# motorController.net
KiCad netlist of a schematic drawn in Altium Designer
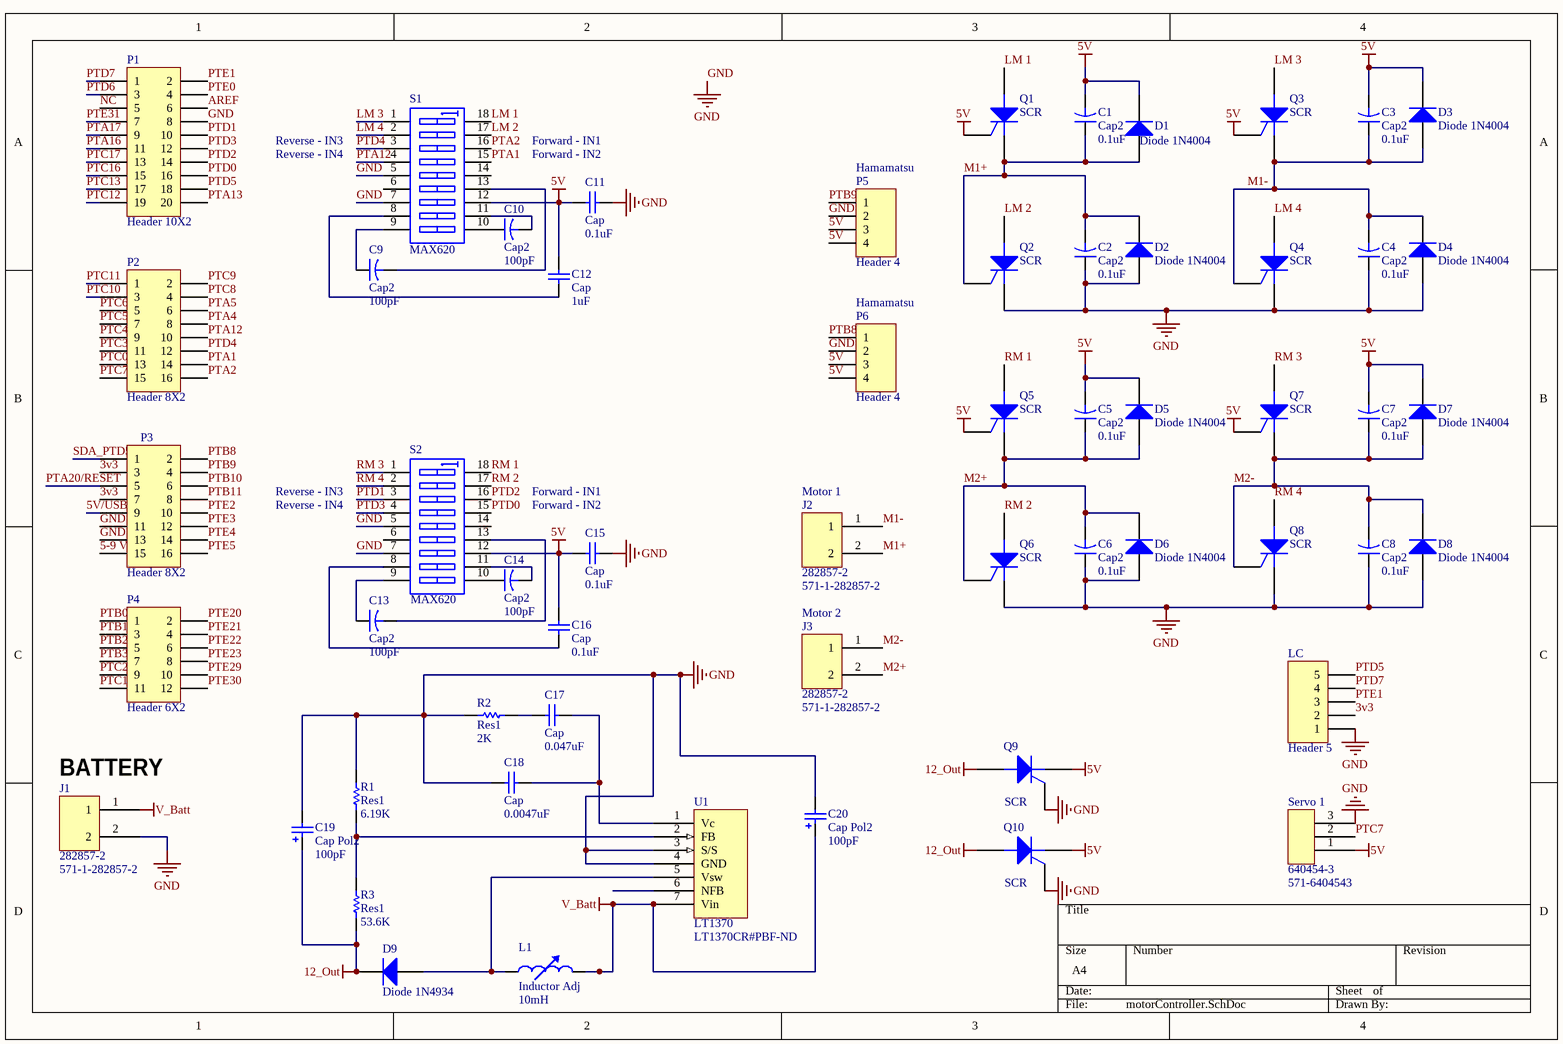
[diagram p0: motorController.SchDoc]

(export (version "E")
  (design (tool "Eeschema 10.0.6"))
  (components
    (comp (ref "C1")
      (value "Cap2")
      (footprint "CAPR5-4X5")
      (description "Capacitor")
      (fields (field (name "ALTIUM_VALUE") "0.1uF") (field (name "PUBLISHER") "Altium Limited"))
      (libsource (lib "Miscellaneous Devices") (part "Cap2"))
    )
    (comp (ref "C2")
      (value "Cap2")
      (footprint "CAPR5-4X5")
      (description "Capacitor")
      (fields (field (name "ALTIUM_VALUE") "0.1uF") (field (name "PUBLISHER") "Altium Limited"))
      (libsource (lib "Miscellaneous Devices") (part "Cap2"))
    )
    (comp (ref "C3")
      (value "Cap2")
      (footprint "CAPR5-4X5")
      (description "Capacitor")
      (fields (field (name "ALTIUM_VALUE") "0.1uF") (field (name "PUBLISHER") "Altium Limited"))
      (libsource (lib "Miscellaneous Devices") (part "Cap2"))
    )
    (comp (ref "C4")
      (value "Cap2")
      (footprint "CAPR5-4X5")
      (description "Capacitor")
      (fields (field (name "ALTIUM_VALUE") "0.1uF") (field (name "PUBLISHER") "Altium Limited"))
      (libsource (lib "Miscellaneous Devices") (part "Cap2"))
    )
    (comp (ref "C5")
      (value "Cap2")
      (footprint "CAPR5-4X5")
      (description "Capacitor")
      (fields (field (name "ALTIUM_VALUE") "0.1uF") (field (name "PUBLISHER") "Altium Limited"))
      (libsource (lib "Miscellaneous Devices") (part "Cap2"))
    )
    (comp (ref "C6")
      (value "Cap2")
      (footprint "CAPR5-4X5")
      (description "Capacitor")
      (fields (field (name "ALTIUM_VALUE") "0.1uF") (field (name "PUBLISHER") "Altium Limited"))
      (libsource (lib "Miscellaneous Devices") (part "Cap2"))
    )
    (comp (ref "C7")
      (value "Cap2")
      (footprint "CAPR5-4X5")
      (description "Capacitor")
      (fields (field (name "ALTIUM_VALUE") "0.1uF") (field (name "PUBLISHER") "Altium Limited"))
      (libsource (lib "Miscellaneous Devices") (part "Cap2"))
    )
    (comp (ref "C8")
      (value "Cap2")
      (footprint "CAPR5-4X5")
      (description "Capacitor")
      (fields (field (name "ALTIUM_VALUE") "0.1uF") (field (name "PUBLISHER") "Altium Limited"))
      (libsource (lib "Miscellaneous Devices") (part "Cap2"))
    )
    (comp (ref "C9")
      (value "Cap2")
      (footprint "CAPR5-4X5")
      (description "Capacitor")
      (fields (field (name "ALTIUM_VALUE") "100pF") (field (name "PUBLISHER") "Altium Limited"))
      (libsource (lib "Miscellaneous Devices") (part "Cap2"))
    )
    (comp (ref "C10")
      (value "Cap2")
      (footprint "CAPR5-4X5")
      (description "Capacitor")
      (fields (field (name "ALTIUM_VALUE") "100pF") (field (name "PUBLISHER") "Altium Limited"))
      (libsource (lib "Miscellaneous Devices") (part "Cap2"))
    )
    (comp (ref "C11")
      (value "Cap")
      (footprint "RAD-0.3")
      (description "Capacitor")
      (fields (field (name "ALTIUM_VALUE") "0.1uF") (field (name "PUBLISHER") "Altium Limited"))
      (libsource (lib "Miscellaneous Devices") (part "Cap"))
    )
    (comp (ref "C12")
      (value "Cap")
      (footprint "RAD-0.3")
      (description "Capacitor")
      (fields (field (name "ALTIUM_VALUE") "1uF") (field (name "PUBLISHER") "Altium Limited"))
      (libsource (lib "Miscellaneous Devices") (part "Cap"))
    )
    (comp (ref "C13")
      (value "Cap2")
      (footprint "CAPR5-4X5")
      (description "Capacitor")
      (fields (field (name "ALTIUM_VALUE") "100pF") (field (name "PUBLISHER") "Altium Limited"))
      (libsource (lib "Miscellaneous Devices") (part "Cap2"))
    )
    (comp (ref "C14")
      (value "Cap2")
      (footprint "CAPR5-4X5")
      (description "Capacitor")
      (fields (field (name "ALTIUM_VALUE") "100pF") (field (name "PUBLISHER") "Altium Limited"))
      (libsource (lib "Miscellaneous Devices") (part "Cap2"))
    )
    (comp (ref "C15")
      (value "Cap")
      (footprint "RAD-0.3")
      (description "Capacitor")
      (fields (field (name "ALTIUM_VALUE") "0.1uF") (field (name "PUBLISHER") "Altium Limited"))
      (libsource (lib "Miscellaneous Devices") (part "Cap"))
    )
    (comp (ref "C16")
      (value "Cap")
      (footprint "RAD-0.3")
      (description "Capacitor")
      (fields (field (name "ALTIUM_VALUE") "0.1uF") (field (name "PUBLISHER") "Altium Limited"))
      (libsource (lib "Miscellaneous Devices") (part "Cap"))
    )
    (comp (ref "C17")
      (value "Cap")
      (footprint "RAD-0.3")
      (description "Capacitor")
      (fields (field (name "ALTIUM_VALUE") "0.047uF") (field (name "PUBLISHER") "Altium Limited"))
      (libsource (lib "Miscellaneous Devices") (part "Cap"))
    )
    (comp (ref "C18")
      (value "Cap")
      (footprint "RAD-0.3")
      (description "Capacitor")
      (fields (field (name "ALTIUM_VALUE") "0.0047uF") (field (name "PUBLISHER") "Altium Limited"))
      (libsource (lib "Miscellaneous Devices") (part "Cap"))
    )
    (comp (ref "C19")
      (value "Cap Pol2")
      (footprint "POLAR0.8")
      (description "Polarized Capacitor (Axial)")
      (fields (field (name "ALTIUM_VALUE") "100pF") (field (name "PUBLISHER") "Altium Limited"))
      (libsource (lib "Miscellaneous Devices") (part "Cap Pol2"))
    )
    (comp (ref "C20")
      (value "Cap Pol2")
      (footprint "POLAR0.8")
      (description "Polarized Capacitor (Axial)")
      (fields (field (name "ALTIUM_VALUE") "100pF") (field (name "PUBLISHER") "Altium Limited"))
      (libsource (lib "Miscellaneous Devices") (part "Cap Pol2"))
    )
    (comp (ref "D1")
      (value "Diode 1N4004")
      (footprint "DO-41")
      (description "1 Amp General Purpose Rectifier")
      (fields (field (name "PUBLISHER") "Altium Limited"))
      (libsource (lib "Miscellaneous Devices") (part "Diode 1N4004"))
    )
    (comp (ref "D2")
      (value "Diode 1N4004")
      (footprint "DO-41")
      (description "1 Amp General Purpose Rectifier")
      (fields (field (name "PUBLISHER") "Altium Limited"))
      (libsource (lib "Miscellaneous Devices") (part "Diode 1N4004"))
    )
    (comp (ref "D3")
      (value "Diode 1N4004")
      (footprint "DO-41")
      (description "1 Amp General Purpose Rectifier")
      (fields (field (name "PUBLISHER") "Altium Limited"))
      (libsource (lib "Miscellaneous Devices") (part "Diode 1N4004"))
    )
    (comp (ref "D4")
      (value "Diode 1N4004")
      (footprint "DO-41")
      (description "1 Amp General Purpose Rectifier")
      (fields (field (name "PUBLISHER") "Altium Limited"))
      (libsource (lib "Miscellaneous Devices") (part "Diode 1N4004"))
    )
    (comp (ref "D5")
      (value "Diode 1N4004")
      (footprint "DO-41")
      (description "1 Amp General Purpose Rectifier")
      (fields (field (name "PUBLISHER") "Altium Limited"))
      (libsource (lib "Miscellaneous Devices") (part "Diode 1N4004"))
    )
    (comp (ref "D6")
      (value "Diode 1N4004")
      (footprint "DO-41")
      (description "1 Amp General Purpose Rectifier")
      (fields (field (name "PUBLISHER") "Altium Limited"))
      (libsource (lib "Miscellaneous Devices") (part "Diode 1N4004"))
    )
    (comp (ref "D7")
      (value "Diode 1N4004")
      (footprint "DO-41")
      (description "1 Amp General Purpose Rectifier")
      (fields (field (name "PUBLISHER") "Altium Limited"))
      (libsource (lib "Miscellaneous Devices") (part "Diode 1N4004"))
    )
    (comp (ref "D8")
      (value "Diode 1N4004")
      (footprint "DO-41")
      (description "1 Amp General Purpose Rectifier")
      (fields (field (name "PUBLISHER") "Altium Limited"))
      (libsource (lib "Miscellaneous Devices") (part "Diode 1N4004"))
    )
    (comp (ref "D9")
      (value "Diode 1N4934")
      (footprint "DO-41")
      (description "1 Amp Fast Recovery Rectifier")
      (fields (field (name "PUBLISHER") "Altium Limited"))
      (libsource (lib "Miscellaneous Devices") (part "Diode 1N4934"))
    )
    (comp (ref "J1")
      (value "282857-2")
      (footprint "282857-2")
      (fields (field (name "SUPPLIER PART NUMBER 1") "571-1-282857-2"))
      (libsource (lib "TE_Connectors") (part "282857-2"))
    )
    (comp (ref "J2")
      (value "282857-2")
      (footprint "282857-2")
      (fields (field (name "SUPPLIER PART NUMBER 1") "571-1-282857-2"))
      (libsource (lib "TE_Connectors") (part "282857-2"))
    )
    (comp (ref "J3")
      (value "282857-2")
      (footprint "282857-2")
      (fields (field (name "SUPPLIER PART NUMBER 1") "571-1-282857-2"))
      (libsource (lib "TE_Connectors") (part "282857-2"))
    )
    (comp (ref "L1")
      (value "Inductor Adj")
      (footprint "AXIAL-0.8")
      (description "Adjustable Inductor")
      (fields (field (name "ALTIUM_VALUE") "10mH") (field (name "PUBLISHER") "Altium Limited"))
      (libsource (lib "Miscellaneous Devices") (part "Inductor Adj"))
    )
    (comp (ref "LC")
      (value "Header 5")
      (footprint "HDR1X5")
      (description "Header, 5-Pin")
      (fields (field (name "PUBLISHER") "Altium Limited"))
      (libsource (lib "Miscellaneous Connectors") (part "Header 5"))
    )
    (comp (ref "P1")
      (value "Header 10X2")
      (footprint "HDR2X10")
      (description "Header, 10-Pin, Dual row")
      (fields (field (name "PUBLISHER") "Altium Limited"))
      (libsource (lib "Miscellaneous Connectors") (part "Header 10X2"))
    )
    (comp (ref "P2")
      (value "Header 8X2")
      (footprint "HDR2X8")
      (description "Header, 8-Pin, Dual row")
      (fields (field (name "PUBLISHER") "Altium Limited"))
      (libsource (lib "Miscellaneous Connectors") (part "Header 8X2"))
    )
    (comp (ref "P3")
      (value "Header 8X2")
      (footprint "HDR2X8")
      (description "Header, 8-Pin, Dual row")
      (fields (field (name "PUBLISHER") "Altium Limited"))
      (libsource (lib "Miscellaneous Connectors") (part "Header 8X2"))
    )
    (comp (ref "P4")
      (value "Header 6X2")
      (footprint "HDR2X6")
      (description "Header, 6-Pin, Dual row")
      (fields (field (name "PUBLISHER") "Altium Limited"))
      (libsource (lib "Miscellaneous Connectors") (part "Header 6X2"))
    )
    (comp (ref "P5")
      (value "Header 4")
      (footprint "HDR1X4")
      (description "Header, 4-Pin")
      (fields (field (name "PUBLISHER") "Altium Limited"))
      (libsource (lib "Miscellaneous Connectors") (part "Header 4"))
    )
    (comp (ref "P6")
      (value "Header 4")
      (footprint "HDR1X4")
      (description "Header, 4-Pin")
      (fields (field (name "PUBLISHER") "Altium Limited"))
      (libsource (lib "Miscellaneous Connectors") (part "Header 4"))
    )
    (comp (ref "Q1")
      (value "SCR")
      (footprint "TO-220-AB")
      (description "Silicon Controlled Rectifier")
      (fields (field (name "PUBLISHER") "Altium Limited"))
      (libsource (lib "Miscellaneous Devices") (part "SCR"))
    )
    (comp (ref "Q2")
      (value "SCR")
      (footprint "TO-220-AB")
      (description "Silicon Controlled Rectifier")
      (fields (field (name "PUBLISHER") "Altium Limited"))
      (libsource (lib "Miscellaneous Devices") (part "SCR"))
    )
    (comp (ref "Q3")
      (value "SCR")
      (footprint "TO-220-AB")
      (description "Silicon Controlled Rectifier")
      (fields (field (name "PUBLISHER") "Altium Limited"))
      (libsource (lib "Miscellaneous Devices") (part "SCR"))
    )
    (comp (ref "Q4")
      (value "SCR")
      (footprint "TO-220-AB")
      (description "Silicon Controlled Rectifier")
      (fields (field (name "PUBLISHER") "Altium Limited"))
      (libsource (lib "Miscellaneous Devices") (part "SCR"))
    )
    (comp (ref "Q5")
      (value "SCR")
      (footprint "TO-220-AB")
      (description "Silicon Controlled Rectifier")
      (fields (field (name "PUBLISHER") "Altium Limited"))
      (libsource (lib "Miscellaneous Devices") (part "SCR"))
    )
    (comp (ref "Q6")
      (value "SCR")
      (footprint "TO-220-AB")
      (description "Silicon Controlled Rectifier")
      (fields (field (name "PUBLISHER") "Altium Limited"))
      (libsource (lib "Miscellaneous Devices") (part "SCR"))
    )
    (comp (ref "Q7")
      (value "SCR")
      (footprint "TO-220-AB")
      (description "Silicon Controlled Rectifier")
      (fields (field (name "PUBLISHER") "Altium Limited"))
      (libsource (lib "Miscellaneous Devices") (part "SCR"))
    )
    (comp (ref "Q8")
      (value "SCR")
      (footprint "TO-220-AB")
      (description "Silicon Controlled Rectifier")
      (fields (field (name "PUBLISHER") "Altium Limited"))
      (libsource (lib "Miscellaneous Devices") (part "SCR"))
    )
    (comp (ref "Q9")
      (value "SCR")
      (footprint "TO-220-AB")
      (description "Silicon Controlled Rectifier")
      (fields (field (name "PUBLISHER") "Altium Limited"))
      (libsource (lib "Miscellaneous Devices") (part "SCR"))
    )
    (comp (ref "Q10")
      (value "SCR")
      (footprint "TO-220-AB")
      (description "Silicon Controlled Rectifier")
      (fields (field (name "PUBLISHER") "Altium Limited"))
      (libsource (lib "Miscellaneous Devices") (part "SCR"))
    )
    (comp (ref "R1")
      (value "Res1")
      (footprint "AXIAL-0.3")
      (description "Resistor")
      (fields (field (name "ALTIUM_VALUE") "6.19K") (field (name "PUBLISHER") "Altium Limited"))
      (libsource (lib "Miscellaneous Devices") (part "Res1"))
    )
    (comp (ref "R2")
      (value "Res1")
      (footprint "AXIAL-0.3")
      (description "Resistor")
      (fields (field (name "ALTIUM_VALUE") "2K") (field (name "PUBLISHER") "Altium Limited"))
      (libsource (lib "Miscellaneous Devices") (part "Res1"))
    )
    (comp (ref "R3")
      (value "Res1")
      (footprint "AXIAL-0.3")
      (description "Resistor")
      (fields (field (name "ALTIUM_VALUE") "53.6K") (field (name "PUBLISHER") "Altium Limited"))
      (libsource (lib "Miscellaneous Devices") (part "Res1"))
    )
    (comp (ref "S1")
      (value "MAX620")
      (footprint "DIP-18")
      (description "DIP Switch, 9 Position, SPST")
      (fields (field (name "PUBLISHER") "Altium Limited"))
      (libsource (lib "Miscellaneous Devices") (part "SW DIP-9"))
    )
    (comp (ref "S2")
      (value "MAX620")
      (footprint "DIP-18")
      (description "DIP Switch, 9 Position, SPST")
      (fields (field (name "PUBLISHER") "Altium Limited"))
      (libsource (lib "Miscellaneous Devices") (part "SW DIP-9"))
    )
    (comp (ref "Servo 1")
      (value "640454-3")
      (footprint "6404543")
      (description "Headers & Wire Housings POLARIZED HEADER 3P Straight Post tin")
      (fields (field (name "SUPPLIER PART NUMBER 1") "571-6404543"))
      (libsource (lib "TE_Connectors") (part "640454-3"))
    )
    (comp (ref "U1")
      (value "LT1370")
      (footprint "DDPak7")
      (fields (field (name "SUPPLIER PART NUMBER 1") "LT1370CR#PBF-ND"))
      (libsource (lib "Switching_Regulators") (part "LT1370"))
    )
  )
  (nets
    (net (code "1") (name "/3v3") (class "Default")
      (node (ref "LC") (pin "2") (pinfunction "2_2") (pintype "passive"))
      (node (ref "P3") (pin "3") (pinfunction "3_3") (pintype "passive"))
      (node (ref "P3") (pin "7") (pinfunction "7_7") (pintype "passive"))
    )
    (net (code "2") (name "/5-9 Vin") (class "Default")
      (node (ref "P3") (pin "15") (pinfunction "15_15") (pintype "passive"))
    )
    (net (code "3") (name "/5V{slash}USB") (class "Default")
      (node (ref "P3") (pin "9") (pinfunction "9_9") (pintype "passive"))
    )
    (net (code "4") (name "/AREF") (class "Default")
      (node (ref "P1") (pin "6") (pinfunction "6_6") (pintype "passive"))
    )
    (net (code "5") (name "/LM 1") (class "Default")
      (node (ref "Q1") (pin "1") (pinfunction "A_1") (pintype "passive"))
      (node (ref "S1") (pin "18") (pinfunction "B1_18") (pintype "passive"))
    )
    (net (code "6") (name "/LM 2") (class "Default")
      (node (ref "Q2") (pin "1") (pinfunction "A_1") (pintype "passive"))
      (node (ref "S1") (pin "17") (pinfunction "B2_17") (pintype "passive"))
    )
    (net (code "7") (name "/LM 3") (class "Default")
      (node (ref "Q3") (pin "1") (pinfunction "A_1") (pintype "passive"))
      (node (ref "S1") (pin "1") (pinfunction "A1_1") (pintype "passive"))
    )
    (net (code "8") (name "/LM 4") (class "Default")
      (node (ref "Q4") (pin "1") (pinfunction "A_1") (pintype "passive"))
      (node (ref "S1") (pin "2") (pinfunction "A2_2") (pintype "passive"))
    )
    (net (code "9") (name "/M1+") (class "Default")
      (node (ref "C1") (pin "1") (pinfunction "1_1") (pintype "passive"))
      (node (ref "C2") (pin "2") (pinfunction "2_2") (pintype "passive"))
      (node (ref "D1") (pin "1") (pinfunction "A_1") (pintype "passive"))
      (node (ref "D2") (pin "2") (pinfunction "K_2") (pintype "passive"))
      (node (ref "J2") (pin "2") (pinfunction "2_2") (pintype "passive"))
      (node (ref "Q1") (pin "3") (pinfunction "K_3") (pintype "passive"))
      (node (ref "Q2") (pin "2") (pinfunction "G_2") (pintype "passive"))
    )
    (net (code "10") (name "/M1-") (class "Default")
      (node (ref "C3") (pin "1") (pinfunction "1_1") (pintype "passive"))
      (node (ref "C4") (pin "2") (pinfunction "2_2") (pintype "passive"))
      (node (ref "D3") (pin "1") (pinfunction "A_1") (pintype "passive"))
      (node (ref "D4") (pin "2") (pinfunction "K_2") (pintype "passive"))
      (node (ref "J2") (pin "1") (pinfunction "1_1") (pintype "passive"))
      (node (ref "Q3") (pin "3") (pinfunction "K_3") (pintype "passive"))
      (node (ref "Q4") (pin "2") (pinfunction "G_2") (pintype "passive"))
    )
    (net (code "11") (name "/M2+") (class "Default")
      (node (ref "C5") (pin "1") (pinfunction "1_1") (pintype "passive"))
      (node (ref "C6") (pin "2") (pinfunction "2_2") (pintype "passive"))
      (node (ref "D5") (pin "1") (pinfunction "A_1") (pintype "passive"))
      (node (ref "D6") (pin "2") (pinfunction "K_2") (pintype "passive"))
      (node (ref "J3") (pin "2") (pinfunction "2_2") (pintype "passive"))
      (node (ref "Q5") (pin "3") (pinfunction "K_3") (pintype "passive"))
      (node (ref "Q6") (pin "2") (pinfunction "G_2") (pintype "passive"))
    )
    (net (code "12") (name "/M2-") (class "Default")
      (node (ref "C7") (pin "1") (pinfunction "1_1") (pintype "passive"))
      (node (ref "C8") (pin "2") (pinfunction "2_2") (pintype "passive"))
      (node (ref "D7") (pin "1") (pinfunction "A_1") (pintype "passive"))
      (node (ref "D8") (pin "2") (pinfunction "K_2") (pintype "passive"))
      (node (ref "J3") (pin "1") (pinfunction "1_1") (pintype "passive"))
      (node (ref "Q7") (pin "3") (pinfunction "K_3") (pintype "passive"))
      (node (ref "Q8") (pin "2") (pinfunction "G_2") (pintype "passive"))
    )
    (net (code "13") (name "/NC") (class "Default")
      (node (ref "P1") (pin "5") (pinfunction "5_5") (pintype "passive"))
    )
    (net (code "14") (name "/PTA1") (class "Default")
      (node (ref "P2") (pin "14") (pinfunction "14_14") (pintype "passive"))
      (node (ref "S1") (pin "15") (pinfunction "B4_15") (pintype "passive"))
    )
    (net (code "15") (name "/PTA2") (class "Default")
      (node (ref "P2") (pin "16") (pinfunction "16_16") (pintype "passive"))
      (node (ref "S1") (pin "16") (pinfunction "B3_16") (pintype "passive"))
    )
    (net (code "16") (name "/PTA4") (class "Default")
      (node (ref "P2") (pin "8") (pinfunction "8_8") (pintype "passive"))
    )
    (net (code "17") (name "/PTA5") (class "Default")
      (node (ref "P2") (pin "6") (pinfunction "6_6") (pintype "passive"))
    )
    (net (code "18") (name "/PTA12") (class "Default")
      (node (ref "P2") (pin "10") (pinfunction "10_10") (pintype "passive"))
      (node (ref "S1") (pin "4") (pinfunction "A4_4") (pintype "passive"))
    )
    (net (code "19") (name "/PTA13") (class "Default")
      (node (ref "P1") (pin "20") (pinfunction "20_20") (pintype "passive"))
    )
    (net (code "20") (name "/PTA16") (class "Default")
      (node (ref "P1") (pin "11") (pinfunction "11_11") (pintype "passive"))
    )
    (net (code "21") (name "/PTA17") (class "Default")
      (node (ref "P1") (pin "9") (pinfunction "9_9") (pintype "passive"))
    )
    (net (code "22") (name "/PTA20{slash}RESET") (class "Default")
      (node (ref "P3") (pin "5") (pinfunction "5_5") (pintype "passive"))
    )
    (net (code "23") (name "/PTB0") (class "Default")
      (node (ref "P4") (pin "1") (pinfunction "1_1") (pintype "passive"))
    )
    (net (code "24") (name "/PTB1") (class "Default")
      (node (ref "P4") (pin "3") (pinfunction "3_3") (pintype "passive"))
    )
    (net (code "25") (name "/PTB2") (class "Default")
      (node (ref "P4") (pin "5") (pinfunction "5_5") (pintype "passive"))
    )
    (net (code "26") (name "/PTB3") (class "Default")
      (node (ref "P4") (pin "7") (pinfunction "7_7") (pintype "passive"))
    )
    (net (code "27") (name "/PTB8") (class "Default")
      (node (ref "P3") (pin "2") (pinfunction "2_2") (pintype "passive"))
      (node (ref "P6") (pin "1") (pinfunction "1_1") (pintype "passive"))
    )
    (net (code "28") (name "/PTB9") (class "Default")
      (node (ref "P3") (pin "4") (pinfunction "4_4") (pintype "passive"))
      (node (ref "P5") (pin "1") (pinfunction "1_1") (pintype "passive"))
    )
    (net (code "29") (name "/PTB10") (class "Default")
      (node (ref "P3") (pin "6") (pinfunction "6_6") (pintype "passive"))
    )
    (net (code "30") (name "/PTB11") (class "Default")
      (node (ref "P3") (pin "8") (pinfunction "8_8") (pintype "passive"))
    )
    (net (code "31") (name "/PTC0") (class "Default")
      (node (ref "P2") (pin "13") (pinfunction "13_13") (pintype "passive"))
    )
    (net (code "32") (name "/PTC1") (class "Default")
      (node (ref "P4") (pin "11") (pinfunction "11_11") (pintype "passive"))
    )
    (net (code "33") (name "/PTC2") (class "Default")
      (node (ref "P4") (pin "9") (pinfunction "9_9") (pintype "passive"))
    )
    (net (code "34") (name "/PTC3") (class "Default")
      (node (ref "P2") (pin "11") (pinfunction "11_11") (pintype "passive"))
    )
    (net (code "35") (name "/PTC4") (class "Default")
      (node (ref "P2") (pin "9") (pinfunction "9_9") (pintype "passive"))
    )
    (net (code "36") (name "/PTC5") (class "Default")
      (node (ref "P2") (pin "7") (pinfunction "7_7") (pintype "passive"))
    )
    (net (code "37") (name "/PTC6") (class "Default")
      (node (ref "P2") (pin "5") (pinfunction "5_5") (pintype "passive"))
    )
    (net (code "38") (name "/PTC7") (class "Default")
      (node (ref "P2") (pin "15") (pinfunction "15_15") (pintype "passive"))
      (node (ref "Servo 1") (pin "2") (pinfunction "2_2") (pintype "passive"))
    )
    (net (code "39") (name "/PTC8") (class "Default")
      (node (ref "P2") (pin "4") (pinfunction "4_4") (pintype "passive"))
    )
    (net (code "40") (name "/PTC9") (class "Default")
      (node (ref "P2") (pin "2") (pinfunction "2_2") (pintype "passive"))
    )
    (net (code "41") (name "/PTC10") (class "Default")
      (node (ref "P2") (pin "3") (pinfunction "3_3") (pintype "passive"))
    )
    (net (code "42") (name "/PTC11") (class "Default")
      (node (ref "P2") (pin "1") (pinfunction "1_1") (pintype "passive"))
    )
    (net (code "43") (name "/PTC12") (class "Default")
      (node (ref "P1") (pin "19") (pinfunction "19_19") (pintype "passive"))
    )
    (net (code "44") (name "/PTC13") (class "Default")
      (node (ref "P1") (pin "17") (pinfunction "17_17") (pintype "passive"))
    )
    (net (code "45") (name "/PTC16") (class "Default")
      (node (ref "P1") (pin "15") (pinfunction "15_15") (pintype "passive"))
    )
    (net (code "46") (name "/PTC17") (class "Default")
      (node (ref "P1") (pin "13") (pinfunction "13_13") (pintype "passive"))
    )
    (net (code "47") (name "/PTD0") (class "Default")
      (node (ref "P1") (pin "16") (pinfunction "16_16") (pintype "passive"))
      (node (ref "S2") (pin "15") (pinfunction "B4_15") (pintype "passive"))
    )
    (net (code "48") (name "/PTD1") (class "Default")
      (node (ref "P1") (pin "10") (pinfunction "10_10") (pintype "passive"))
      (node (ref "S2") (pin "3") (pinfunction "A3_3") (pintype "passive"))
    )
    (net (code "49") (name "/PTD2") (class "Default")
      (node (ref "P1") (pin "14") (pinfunction "14_14") (pintype "passive"))
      (node (ref "S2") (pin "16") (pinfunction "B3_16") (pintype "passive"))
    )
    (net (code "50") (name "/PTD3") (class "Default")
      (node (ref "P1") (pin "12") (pinfunction "12_12") (pintype "passive"))
      (node (ref "S2") (pin "4") (pinfunction "A4_4") (pintype "passive"))
    )
    (net (code "51") (name "/PTD4") (class "Default")
      (node (ref "P2") (pin "12") (pinfunction "12_12") (pintype "passive"))
      (node (ref "S1") (pin "3") (pinfunction "A3_3") (pintype "passive"))
    )
    (net (code "52") (name "/PTD5") (class "Default")
      (node (ref "LC") (pin "5") (pinfunction "5_5") (pintype "passive"))
      (node (ref "P1") (pin "18") (pinfunction "18_18") (pintype "passive"))
    )
    (net (code "53") (name "/PTD6") (class "Default")
      (node (ref "P1") (pin "3") (pinfunction "3_3") (pintype "passive"))
    )
    (net (code "54") (name "/PTD7") (class "Default")
      (node (ref "LC") (pin "4") (pinfunction "4_4") (pintype "passive"))
      (node (ref "P1") (pin "1") (pinfunction "1_1") (pintype "passive"))
    )
    (net (code "55") (name "/PTE0") (class "Default")
      (node (ref "P1") (pin "4") (pinfunction "4_4") (pintype "passive"))
    )
    (net (code "56") (name "/PTE1") (class "Default")
      (node (ref "LC") (pin "3") (pinfunction "3_3") (pintype "passive"))
      (node (ref "P1") (pin "2") (pinfunction "2_2") (pintype "passive"))
    )
    (net (code "57") (name "/PTE2") (class "Default")
      (node (ref "P3") (pin "10") (pinfunction "10_10") (pintype "passive"))
    )
    (net (code "58") (name "/PTE3") (class "Default")
      (node (ref "P3") (pin "12") (pinfunction "12_12") (pintype "passive"))
    )
    (net (code "59") (name "/PTE4") (class "Default")
      (node (ref "P3") (pin "14") (pinfunction "14_14") (pintype "passive"))
    )
    (net (code "60") (name "/PTE5") (class "Default")
      (node (ref "P3") (pin "16") (pinfunction "16_16") (pintype "passive"))
    )
    (net (code "61") (name "/PTE20") (class "Default")
      (node (ref "P4") (pin "2") (pinfunction "2_2") (pintype "passive"))
    )
    (net (code "62") (name "/PTE21") (class "Default")
      (node (ref "P4") (pin "4") (pinfunction "4_4") (pintype "passive"))
    )
    (net (code "63") (name "/PTE22") (class "Default")
      (node (ref "P4") (pin "6") (pinfunction "6_6") (pintype "passive"))
    )
    (net (code "64") (name "/PTE23") (class "Default")
      (node (ref "P4") (pin "8") (pinfunction "8_8") (pintype "passive"))
    )
    (net (code "65") (name "/PTE29") (class "Default")
      (node (ref "P4") (pin "10") (pinfunction "10_10") (pintype "passive"))
    )
    (net (code "66") (name "/PTE30") (class "Default")
      (node (ref "P4") (pin "12") (pinfunction "12_12") (pintype "passive"))
    )
    (net (code "67") (name "/PTE31") (class "Default")
      (node (ref "P1") (pin "7") (pinfunction "7_7") (pintype "passive"))
    )
    (net (code "68") (name "/RM 1") (class "Default")
      (node (ref "Q5") (pin "1") (pinfunction "A_1") (pintype "passive"))
      (node (ref "S2") (pin "18") (pinfunction "B1_18") (pintype "passive"))
    )
    (net (code "69") (name "/RM 2") (class "Default")
      (node (ref "Q6") (pin "1") (pinfunction "A_1") (pintype "passive"))
      (node (ref "S2") (pin "17") (pinfunction "B2_17") (pintype "passive"))
    )
    (net (code "70") (name "/RM 3") (class "Default")
      (node (ref "Q7") (pin "1") (pinfunction "A_1") (pintype "passive"))
      (node (ref "S2") (pin "1") (pinfunction "A1_1") (pintype "passive"))
    )
    (net (code "71") (name "/RM 4") (class "Default")
      (node (ref "Q8") (pin "1") (pinfunction "A_1") (pintype "passive"))
      (node (ref "S2") (pin "2") (pinfunction "A2_2") (pintype "passive"))
    )
    (net (code "72") (name "/SDA_PTD5") (class "Default")
      (node (ref "P3") (pin "1") (pinfunction "1_1") (pintype "passive"))
    )
    (net (code "73") (name "5V") (class "Default")
      (node (ref "C1") (pin "2") (pinfunction "2_2") (pintype "passive"))
      (node (ref "C11") (pin "1") (pinfunction "1_1") (pintype "passive"))
      (node (ref "C12") (pin "2") (pinfunction "2_2") (pintype "passive"))
      (node (ref "C15") (pin "1") (pinfunction "1_1") (pintype "passive"))
      (node (ref "C16") (pin "2") (pinfunction "2_2") (pintype "passive"))
      (node (ref "C3") (pin "2") (pinfunction "2_2") (pintype "passive"))
      (node (ref "C5") (pin "2") (pinfunction "2_2") (pintype "passive"))
      (node (ref "C7") (pin "2") (pinfunction "2_2") (pintype "passive"))
      (node (ref "D1") (pin "2") (pinfunction "K_2") (pintype "passive"))
      (node (ref "D3") (pin "2") (pinfunction "K_2") (pintype "passive"))
      (node (ref "D5") (pin "2") (pinfunction "K_2") (pintype "passive"))
      (node (ref "D7") (pin "2") (pinfunction "K_2") (pintype "passive"))
      (node (ref "P5") (pin "3") (pinfunction "3_3") (pintype "passive"))
      (node (ref "P5") (pin "4") (pinfunction "4_4") (pintype "passive"))
      (node (ref "P6") (pin "3") (pinfunction "3_3") (pintype "passive"))
      (node (ref "P6") (pin "4") (pinfunction "4_4") (pintype "passive"))
      (node (ref "Q1") (pin "2") (pinfunction "G_2") (pintype "passive"))
      (node (ref "Q10") (pin "3") (pinfunction "K_3") (pintype "passive"))
      (node (ref "Q3") (pin "2") (pinfunction "G_2") (pintype "passive"))
      (node (ref "Q5") (pin "2") (pinfunction "G_2") (pintype "passive"))
      (node (ref "Q7") (pin "2") (pinfunction "G_2") (pintype "passive"))
      (node (ref "Q9") (pin "3") (pinfunction "K_3") (pintype "passive"))
      (node (ref "S1") (pin "12") (pinfunction "B7_12") (pintype "passive"))
      (node (ref "S2") (pin "12") (pinfunction "B7_12") (pintype "passive"))
      (node (ref "Servo 1") (pin "1") (pinfunction "1_1") (pintype "passive"))
    )
    (net (code "74") (name "12_Out") (class "Default")
      (node (ref "C19") (pin "1") (pinfunction "1_1") (pintype "passive"))
      (node (ref "D9") (pin "2") (pinfunction "K_2") (pintype "passive"))
      (node (ref "Q10") (pin "1") (pinfunction "A_1") (pintype "passive"))
      (node (ref "Q9") (pin "1") (pinfunction "A_1") (pintype "passive"))
      (node (ref "R3") (pin "2") (pinfunction "2_2") (pintype "passive"))
    )
    (net (code "75") (name "GND") (class "Default")
      (node (ref "C11") (pin "2") (pinfunction "2_2") (pintype "passive"))
      (node (ref "C15") (pin "2") (pinfunction "2_2") (pintype "passive"))
      (node (ref "C18") (pin "1") (pinfunction "1_1") (pintype "passive"))
      (node (ref "C19") (pin "2") (pinfunction "2_2") (pintype "passive"))
      (node (ref "C2") (pin "1") (pinfunction "1_1") (pintype "passive"))
      (node (ref "C20") (pin "2") (pinfunction "2_2") (pintype "passive"))
      (node (ref "C4") (pin "1") (pinfunction "1_1") (pintype "passive"))
      (node (ref "C6") (pin "1") (pinfunction "1_1") (pintype "passive"))
      (node (ref "C8") (pin "1") (pinfunction "1_1") (pintype "passive"))
      (node (ref "D2") (pin "1") (pinfunction "A_1") (pintype "passive"))
      (node (ref "D4") (pin "1") (pinfunction "A_1") (pintype "passive"))
      (node (ref "D6") (pin "1") (pinfunction "A_1") (pintype "passive"))
      (node (ref "D8") (pin "1") (pinfunction "A_1") (pintype "passive"))
      (node (ref "J1") (pin "2") (pinfunction "2_2") (pintype "passive"))
      (node (ref "LC") (pin "1") (pinfunction "1_1") (pintype "passive"))
      (node (ref "P1") (pin "8") (pinfunction "8_8") (pintype "passive"))
      (node (ref "P3") (pin "11") (pinfunction "11_11") (pintype "passive"))
      (node (ref "P3") (pin "13") (pinfunction "13_13") (pintype "passive"))
      (node (ref "P5") (pin "2") (pinfunction "2_2") (pintype "passive"))
      (node (ref "P6") (pin "2") (pinfunction "2_2") (pintype "passive"))
      (node (ref "Q10") (pin "2") (pinfunction "G_2") (pintype "passive"))
      (node (ref "Q2") (pin "3") (pinfunction "K_3") (pintype "passive"))
      (node (ref "Q4") (pin "3") (pinfunction "K_3") (pintype "passive"))
      (node (ref "Q6") (pin "3") (pinfunction "K_3") (pintype "passive"))
      (node (ref "Q8") (pin "3") (pinfunction "K_3") (pintype "passive"))
      (node (ref "Q9") (pin "2") (pinfunction "G_2") (pintype "passive"))
      (node (ref "R1") (pin "1") (pinfunction "1_1") (pintype "passive"))
      (node (ref "R2") (pin "1") (pinfunction "1_1") (pintype "passive"))
      (node (ref "S1") (pin "5") (pinfunction "A5_5") (pintype "passive"))
      (node (ref "S1") (pin "7") (pinfunction "A7_7") (pintype "passive"))
      (node (ref "S2") (pin "5") (pinfunction "A5_5") (pintype "passive"))
      (node (ref "S2") (pin "7") (pinfunction "A7_7") (pintype "passive"))
      (node (ref "Servo 1") (pin "3") (pinfunction "3_3") (pintype "passive"))
      (node (ref "U1") (pin "3") (pinfunction "S/S_3") (pintype "input"))
      (node (ref "U1") (pin "4") (pinfunction "GND_4") (pintype "power_in"))
    )
    (net (code "76") (name "Net-(C17-Pad1)") (class "Default")
      (node (ref "C17") (pin "1") (pinfunction "1_1") (pintype "passive"))
      (node (ref "R2") (pin "2") (pinfunction "2_2") (pintype "passive"))
    )
    (net (code "77") (name "Net-(D9-A)") (class "Default")
      (node (ref "D9") (pin "1") (pinfunction "A_1") (pintype "passive"))
      (node (ref "L1") (pin "1") (pinfunction "1_1") (pintype "passive"))
      (node (ref "U1") (pin "5") (pinfunction "Vsw_5") (pintype "power_in"))
    )
    (net (code "78") (name "Net-(S1-A8)") (class "Default")
      (node (ref "C12") (pin "1") (pinfunction "1_1") (pintype "passive"))
      (node (ref "S1") (pin "8") (pinfunction "A8_8") (pintype "passive"))
    )
    (net (code "79") (name "Net-(S1-A9)") (class "Default")
      (node (ref "C9") (pin "1") (pinfunction "1_1") (pintype "passive"))
      (node (ref "S1") (pin "9") (pinfunction "A9_9") (pintype "passive"))
    )
    (net (code "80") (name "Net-(S1-B6)") (class "Default")
      (node (ref "C9") (pin "2") (pinfunction "2_2") (pintype "passive"))
      (node (ref "S1") (pin "13") (pinfunction "B6_13") (pintype "passive"))
    )
    (net (code "81") (name "Net-(S1-B8)") (class "Default")
      (node (ref "C10") (pin "2") (pinfunction "2_2") (pintype "passive"))
      (node (ref "S1") (pin "11") (pinfunction "B8_11") (pintype "passive"))
    )
    (net (code "82") (name "Net-(S1-B9)") (class "Default")
      (node (ref "C10") (pin "1") (pinfunction "1_1") (pintype "passive"))
      (node (ref "S1") (pin "10") (pinfunction "B9_10") (pintype "passive"))
    )
    (net (code "83") (name "Net-(S2-A8)") (class "Default")
      (node (ref "C16") (pin "1") (pinfunction "1_1") (pintype "passive"))
      (node (ref "S2") (pin "8") (pinfunction "A8_8") (pintype "passive"))
    )
    (net (code "84") (name "Net-(S2-A9)") (class "Default")
      (node (ref "C13") (pin "1") (pinfunction "1_1") (pintype "passive"))
      (node (ref "S2") (pin "9") (pinfunction "A9_9") (pintype "passive"))
    )
    (net (code "85") (name "Net-(S2-B6)") (class "Default")
      (node (ref "C13") (pin "2") (pinfunction "2_2") (pintype "passive"))
      (node (ref "S2") (pin "13") (pinfunction "B6_13") (pintype "passive"))
    )
    (net (code "86") (name "Net-(S2-B8)") (class "Default")
      (node (ref "C14") (pin "2") (pinfunction "2_2") (pintype "passive"))
      (node (ref "S2") (pin "11") (pinfunction "B8_11") (pintype "passive"))
    )
    (net (code "87") (name "Net-(S2-B9)") (class "Default")
      (node (ref "C14") (pin "1") (pinfunction "1_1") (pintype "passive"))
      (node (ref "S2") (pin "10") (pinfunction "B9_10") (pintype "passive"))
    )
    (net (code "88") (name "Net-(U1-FB)") (class "Default")
      (node (ref "R1") (pin "2") (pinfunction "2_2") (pintype "passive"))
      (node (ref "R3") (pin "1") (pinfunction "1_1") (pintype "passive"))
      (node (ref "U1") (pin "2") (pinfunction "FB_2") (pintype "input"))
    )
    (net (code "89") (name "Net-(U1-Vc)") (class "Default")
      (node (ref "C17") (pin "2") (pinfunction "2_2") (pintype "passive"))
      (node (ref "C18") (pin "2") (pinfunction "2_2") (pintype "passive"))
      (node (ref "U1") (pin "1") (pinfunction "Vc_1") (pintype "power_in"))
    )
    (net (code "90") (name "V_Batt") (class "Default")
      (node (ref "C20") (pin "1") (pinfunction "1_1") (pintype "passive"))
      (node (ref "J1") (pin "1") (pinfunction "1_1") (pintype "passive"))
      (node (ref "L1") (pin "2") (pinfunction "2_2") (pintype "passive"))
      (node (ref "U1") (pin "7") (pinfunction "Vin_7") (pintype "power_in"))
    )
    (net (code "91") (name "unconnected-(S1-A6-Pad6)") (class "Default")
      (node (ref "S1") (pin "6") (pinfunction "A6_6") (pintype "passive"))
    )
    (net (code "92") (name "unconnected-(S1-B5-Pad14)") (class "Default")
      (node (ref "S1") (pin "14") (pinfunction "B5_14") (pintype "passive"))
    )
    (net (code "93") (name "unconnected-(S2-A6-Pad6)") (class "Default")
      (node (ref "S2") (pin "6") (pinfunction "A6_6") (pintype "passive"))
    )
    (net (code "94") (name "unconnected-(S2-B5-Pad14)") (class "Default")
      (node (ref "S2") (pin "14") (pinfunction "B5_14") (pintype "passive"))
    )
    (net (code "95") (name "unconnected-(U1-NFB-Pad6)") (class "Default")
      (node (ref "U1") (pin "6") (pinfunction "NFB_6") (pintype "open_collector"))
    )
  )
)
